# 05_Power.net
KiCad netlist of a schematic drawn in Altium Designer
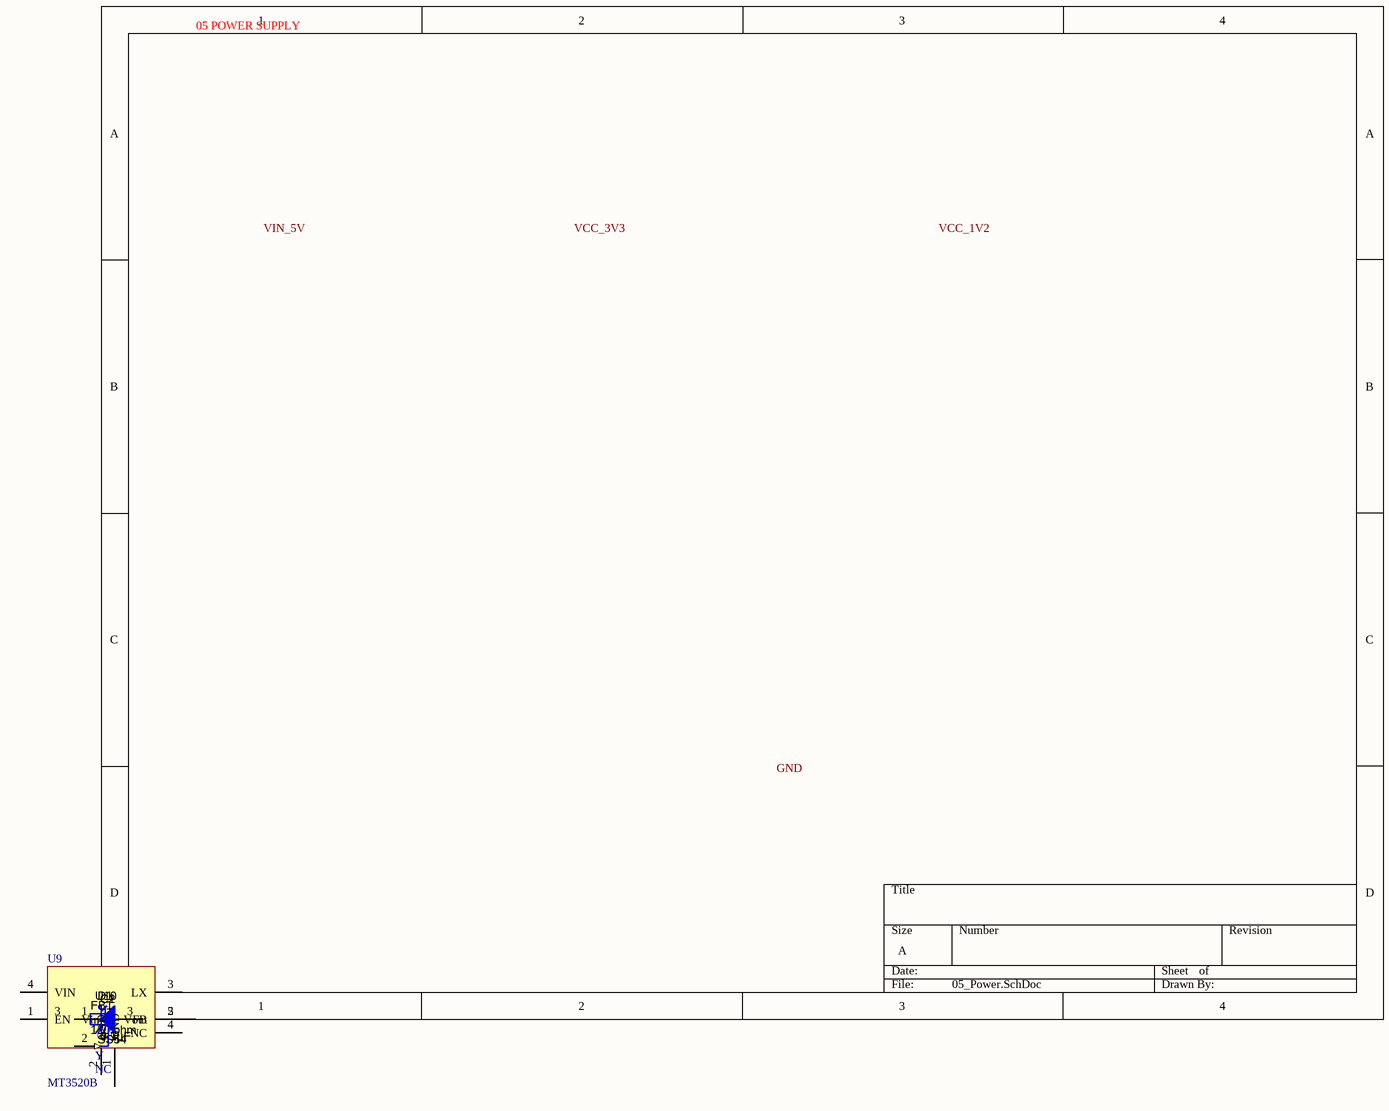
[diagram p0: 05_Power.SchDoc]

(export (version "E")
  (design (tool "Eeschema 10.0.6"))
  (components
    (comp (ref "C1")
      (value "GRM21BC81C475KA88L")
      (footprint "0805_HV")
      (description "CAP, CERM, 4.7 µF, 16 V, +/- 10%, X6S, 0805")
      (fields
        (field (name "VALUEDISPLAYED") "4.7µF")
        (field (name "MANUFACTURER") "MuRata")
        (field (name "PUBLISHER") "Texas Instruments")
      )
      (libsource (lib "Capacitor_Ceramic") (part "GRM21BC81C475KA88L"))
    )
    (comp (ref "C2")
      (value "C1005X7R1H104M")
      (footprint "0402")
      (description "CAP, CERM, 0.1 μF, 50 V, +/- 20%, X7R, 0402")
      (fields
        (field (name "VALUEDISPLAYED") "0.1μF")
        (field (name "MANUFACTURER") "TDK")
        (field (name "PUBLISHER") "Texas Instruments")
      )
      (libsource (lib "Capacitor_Ceramic") (part "C1005X7R1H104M_1"))
    )
    (comp (ref "D1")
      (value "SS54")
      (footprint "SMB")
      (description "Diode, Schottky, 40 V, 3A, SMB")
      (fields (field (name "MANUFACTURER") "Diodes Inc.") (field (name "PUBLISHER") "Texas Instruments"))
      (libsource (lib "Diode") (part "B340B-13-F"))
    )
    (comp (ref "FB1")
      (value "120 ohm")
      (footprint "0805_HV")
      (description "Ferrite Bead, 120 ohm @ 100 MHz, 0.2 A, 0805")
      (fields
        (field (name "PARTNUMBER") "GZ2012V121TF")
        (field (name "MANUFACTURER") "MuRata")
        (field (name "PUBLISHER") "Texas Instruments")
      )
      (libsource (lib "FerriteBead") (part "BLM21BD121SN1D"))
    )
    (comp (ref "U8")
      (value "LD1117-3.3")
      (footprint "控制电路PCB_器件库_V1.0:SOT223-L")
      (description "LDO电源")
      (libsource (lib "控制电路原理图_器件库_V1.0") (part "AMS1117"))
    )
    (comp (ref "U9")
      (value "MT3520B")
      (footprint "DBV0005A_N")
      (description "1MHZ,2A,STEP-DOWM DC/DC")
      (libsource (lib "YQPOWER") (part "RT8097"))
    )
    (comp (ref "U10")
      (value "Y")
      (footprint "DBZ0003A_N")
      (description "PRECISION PROGRAMMABLE REFERENCE, DBZ0003A")
      (fields
        (field (name "PARTNUMBER") "TL431AIDBZ")
        (field (name "MANUFACTURER") "Texas Instruments")
        (field (name "IGNORE") "Y")
        (field (name "PARAMETER 1") "NC")
        (field (name "SYMBOLCREATOR") "a0412235")
        (field (name "PUBLISHER") "Texas Instruments")
      )
      (libsource (lib "TI_Pre_Release") (part "TL431AIDBZ"))
    )
  )
  (nets
    (net (code "5") (name "Net-(C1-Pad1)") (class "Default")
      (node (ref "C1") (pin "1") (pinfunction "1_1") (pintype "passive"))
      (node (ref "C2") (pin "1") (pinfunction "1_1") (pintype "passive"))
    )
    (net (code "6") (name "Net-(C1-Pad2)") (class "Default")
      (node (ref "C1") (pin "2") (pinfunction "2_2") (pintype "passive"))
      (node (ref "C2") (pin "2") (pinfunction "2_2") (pintype "passive"))
      (node (ref "FB1") (pin "1") (pinfunction "1_1") (pintype "passive"))
    )
    (net (code "7") (name "Net-(D1-A)") (class "Default")
      (node (ref "D1") (pin "2") (pinfunction "A_2") (pintype "passive"))
      (node (ref "U10") (pin "3") (pinfunction "ANODE_3") (pintype "passive"))
    )
    (net (code "8") (name "Net-(D1-K)") (class "Default")
      (node (ref "D1") (pin "1") (pinfunction "K_1") (pintype "passive"))
      (node (ref "U10") (pin "1") (pinfunction "CATHODE_1") (pintype "passive"))
    )
    (net (code "9") (name "unconnected-(FB1-Pad2)") (class "Default")
      (node (ref "FB1") (pin "2") (pinfunction "2_2") (pintype "passive"))
    )
    (net (code "10") (name "unconnected-(U8-GND-Pad1)") (class "Default")
      (node (ref "U8") (pin "1") (pinfunction "GND_1") (pintype "power_in"))
    )
    (net (code "11") (name "unconnected-(U8-NC-Pad4)") (class "Default")
      (node (ref "U8") (pin "4") (pinfunction "NC_4") (pintype "passive"))
    )
    (net (code "12") (name "unconnected-(U8-Vin-Pad3)") (class "Default")
      (node (ref "U8") (pin "3") (pinfunction "Vin_3") (pintype "input"))
    )
    (net (code "13") (name "unconnected-(U8-Vout-Pad2)") (class "Default")
      (node (ref "U8") (pin "2") (pinfunction "Vout_2") (pintype "power_in"))
    )
    (net (code "14") (name "unconnected-(U9-EN-Pad1)") (class "Default")
      (node (ref "U9") (pin "1") (pinfunction "EN_1") (pintype "passive"))
    )
    (net (code "15") (name "unconnected-(U9-FB-Pad5)") (class "Default")
      (node (ref "U9") (pin "5") (pinfunction "FB_5") (pintype "passive"))
    )
    (net (code "16") (name "unconnected-(U9-GND-Pad2)") (class "Default")
      (node (ref "U9") (pin "2") (pinfunction "GND_2") (pintype "passive"))
    )
    (net (code "17") (name "unconnected-(U9-LX-Pad3)") (class "Default")
      (node (ref "U9") (pin "3") (pinfunction "LX_3") (pintype "passive"))
    )
    (net (code "18") (name "unconnected-(U9-VIN-Pad4)") (class "Default")
      (node (ref "U9") (pin "4") (pinfunction "VIN_4") (pintype "passive"))
    )
    (net (code "19") (name "unconnected-(U10-REF-Pad2)") (class "Default")
      (node (ref "U10") (pin "2") (pinfunction "REF_2") (pintype "input"))
    )
  )
)
